# ring_indicator.net
KiCad netlist of a schematic drawn in EAGLE
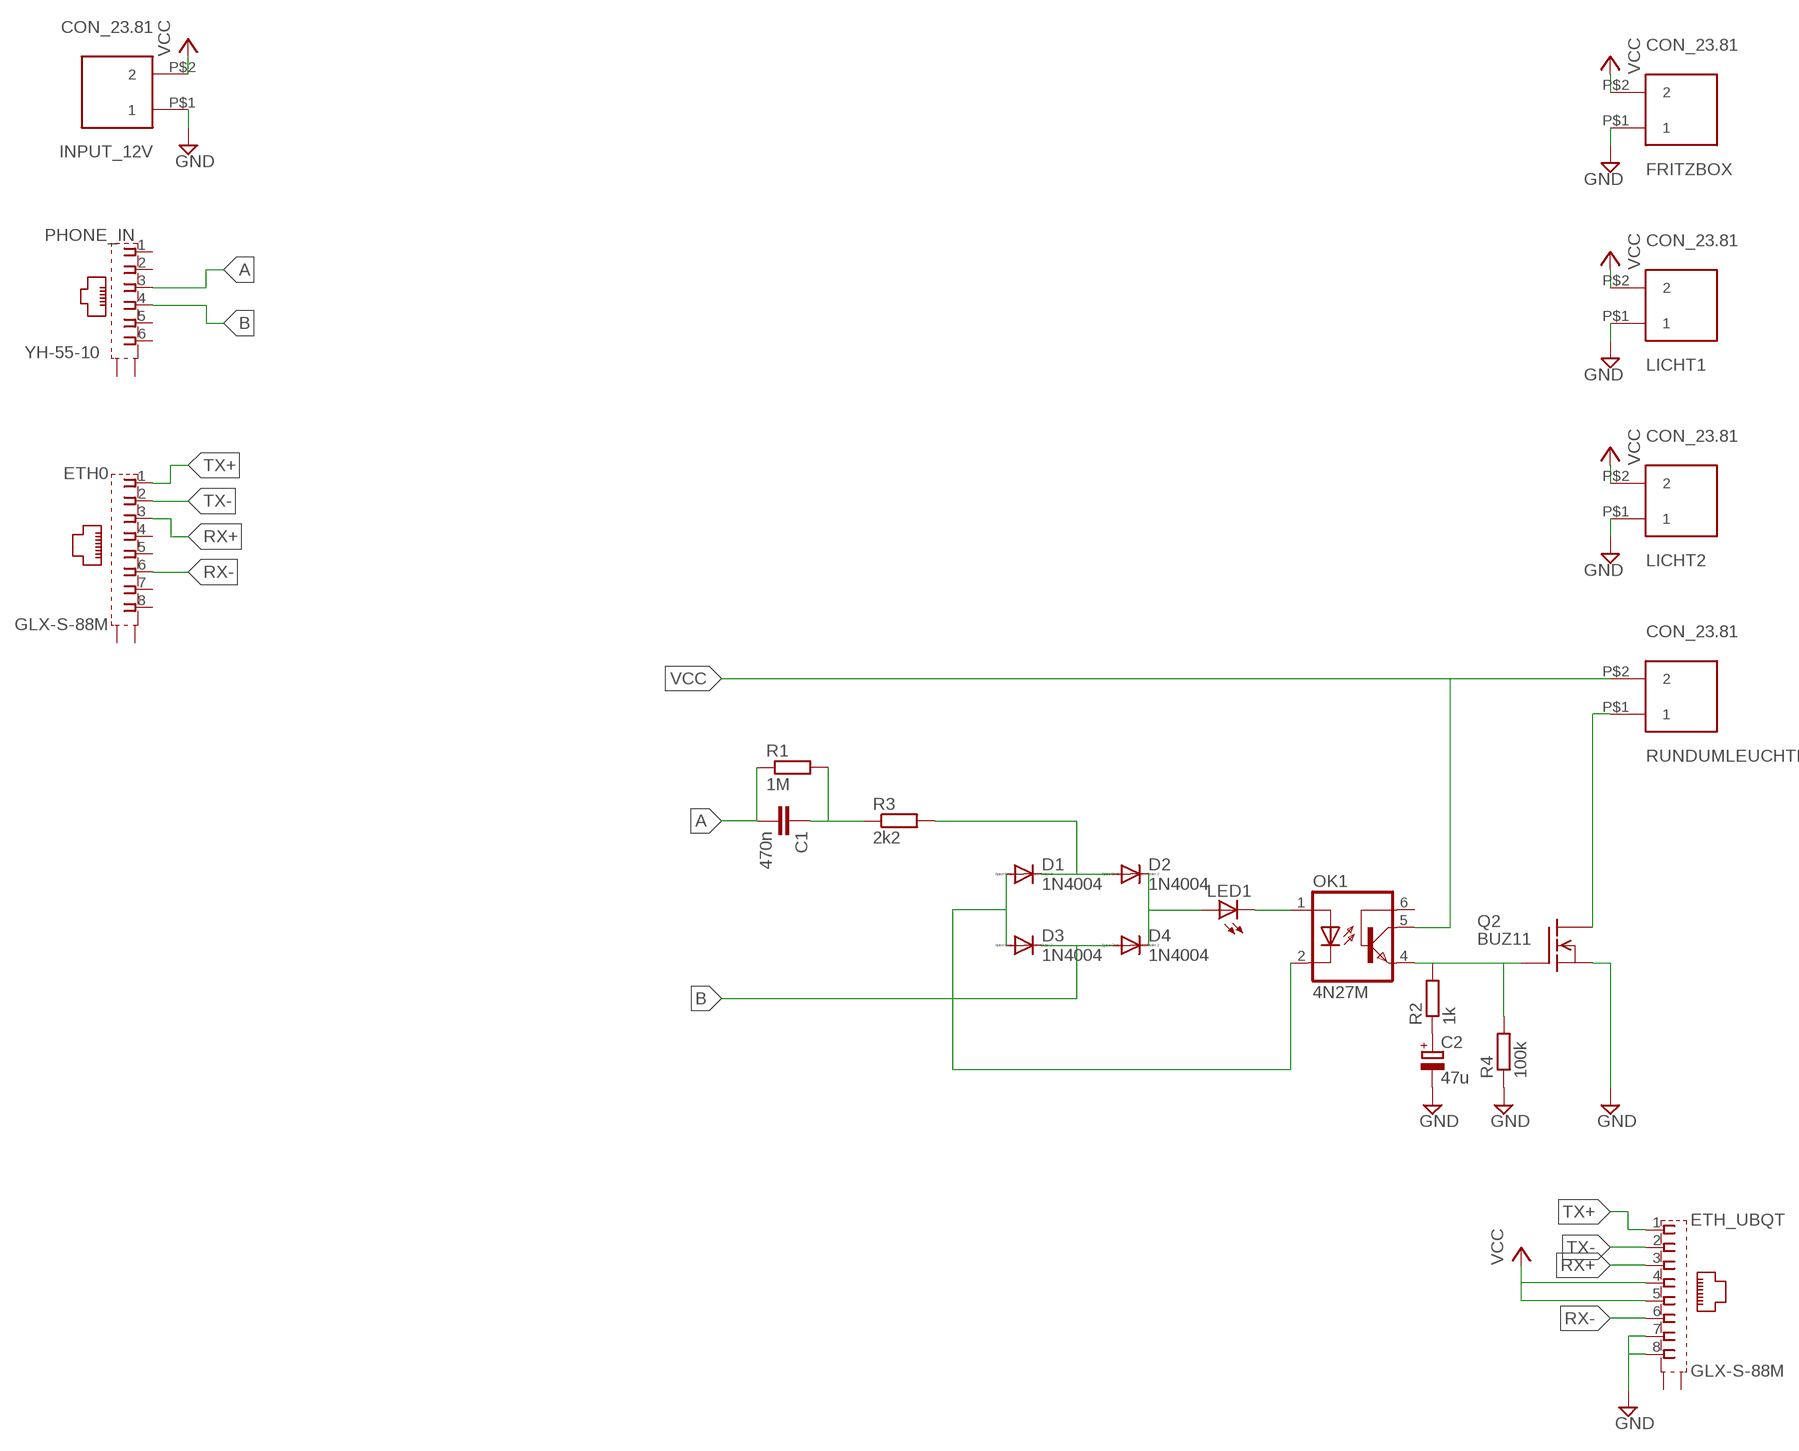
[diagram p0: schematic, sheet 1]

(export (version "E")
  (design (tool "Eeschema 10.0.6"))
  (components
    (comp (ref "C1")
      (value "470n")
      (footprint "eagle-import:C102-064X133")
      (libsource (lib "eagle-import") (part "C-EU102-064X133"))
    )
    (comp (ref "C2")
      (value "47u")
      (footprint "eagle-import:E3,5-8")
      (libsource (lib "eagle-import") (part "CPOL-EUE3.5-8"))
    )
    (comp (ref "D1")
      (value "1N4004")
      (footprint "eagle-import:DO41-10")
      (libsource (lib "eagle-import") (part "1N4004"))
    )
    (comp (ref "D2")
      (value "1N4004")
      (footprint "eagle-import:DO41-10")
      (libsource (lib "eagle-import") (part "1N4004"))
    )
    (comp (ref "D3")
      (value "1N4004")
      (footprint "eagle-import:DO41-10")
      (libsource (lib "eagle-import") (part "1N4004"))
    )
    (comp (ref "D4")
      (value "1N4004")
      (footprint "eagle-import:DO41-10")
      (libsource (lib "eagle-import") (part "1N4004"))
    )
    (comp (ref "ETH0")
      (value "GLX-S-88M")
      (footprint "eagle-import:GLX-S-88M")
      (libsource (lib "eagle-import") (part "GLX-S-88M"))
    )
    (comp (ref "ETH_UBQT")
      (value "GLX-S-88M")
      (footprint "eagle-import:GLX-S-88M")
      (libsource (lib "eagle-import") (part "GLX-S-88M"))
    )
    (comp (ref "FRITZBOX")
      (value "CON_23.81")
      (footprint "eagle-import:CON_2_3.81")
      (libsource (lib "eagle-import") (part "CON_23.81"))
    )
    (comp (ref "INPUT_12V")
      (value "CON_23.81")
      (footprint "eagle-import:CON_2_3.81")
      (libsource (lib "eagle-import") (part "CON_23.81"))
    )
    (comp (ref "LED1")
      (value "LED5MM")
      (footprint "eagle-import:LED5MM")
      (libsource (lib "eagle-import") (part "LED5MM"))
    )
    (comp (ref "LICHT1")
      (value "CON_23.81")
      (footprint "eagle-import:CON_2_3.81")
      (libsource (lib "eagle-import") (part "CON_23.81"))
    )
    (comp (ref "LICHT2")
      (value "CON_23.81")
      (footprint "eagle-import:CON_2_3.81")
      (libsource (lib "eagle-import") (part "CON_23.81"))
    )
    (comp (ref "OK1")
      (value "4N27M")
      (footprint "eagle-import:DIL06")
      (fields (field (name "MF") "FAIRCHILD SEMICONDUCTOR"))
      (libsource (lib "eagle-import") (part "4N?M27"))
    )
    (comp (ref "PHONE_IN")
      (value "YH-55-10")
      (footprint "eagle-import:YH-55-10")
      (libsource (lib "eagle-import") (part "YH-55-10"))
    )
    (comp (ref "Q2")
      (value "BUZ11")
      (footprint "eagle-import:TO220")
      (libsource (lib "eagle-import") (part "BUZ11"))
    )
    (comp (ref "R1")
      (value "1M")
      (footprint "eagle-import:0207_10")
      (libsource (lib "eagle-import") (part "R-EU_0207/10"))
    )
    (comp (ref "R2")
      (value "1k")
      (footprint "eagle-import:0207_10")
      (libsource (lib "eagle-import") (part "R-EU_0207/10"))
    )
    (comp (ref "R3")
      (value "2k2")
      (footprint "eagle-import:0207_10")
      (libsource (lib "eagle-import") (part "R-EU_0207/10"))
    )
    (comp (ref "R4")
      (value "100k")
      (footprint "eagle-import:0207_10")
      (libsource (lib "eagle-import") (part "R-EU_0207/10"))
    )
    (comp (ref "RUNDUMLEUCHTE")
      (value "CON_23.81")
      (footprint "eagle-import:CON_2_3.81")
      (libsource (lib "eagle-import") (part "CON_23.81"))
    )
  )
  (nets
    (net (code "1") (name "A") (class "Default")
      (node (ref "C1") (pin "2") (pinfunction "2_2") (pintype "passive"))
      (node (ref "PHONE_IN") (pin "3") (pinfunction "3_3") (pintype "passive"))
      (node (ref "R1") (pin "1") (pinfunction "1_1") (pintype "passive"))
    )
    (net (code "2") (name "B") (class "Default")
      (node (ref "D3") (pin "C") (pinfunction "C_C") (pintype "passive"))
      (node (ref "D4") (pin "A") (pinfunction "A_A") (pintype "passive"))
      (node (ref "PHONE_IN") (pin "4") (pinfunction "4_4") (pintype "passive"))
    )
    (net (code "3") (name "GND") (class "Default")
      (node (ref "C2") (pin "-") (pinfunction "-_-") (pintype "passive"))
      (node (ref "ETH_UBQT") (pin "7") (pinfunction "7_7") (pintype "passive"))
      (node (ref "ETH_UBQT") (pin "8") (pinfunction "8_8") (pintype "passive"))
      (node (ref "FRITZBOX") (pin "P$1") (pinfunction "1_P$1") (pintype "bidirectional"))
      (node (ref "INPUT_12V") (pin "P$1") (pinfunction "1_P$1") (pintype "bidirectional"))
      (node (ref "LICHT1") (pin "P$1") (pinfunction "1_P$1") (pintype "bidirectional"))
      (node (ref "LICHT2") (pin "P$1") (pinfunction "1_P$1") (pintype "bidirectional"))
      (node (ref "Q2") (pin "3") (pinfunction "S_3") (pintype "passive"))
      (node (ref "R4") (pin "1") (pinfunction "1_1") (pintype "passive"))
    )
    (net (code "4") (name "Net-(C1-Pad1)") (class "Default")
      (node (ref "C1") (pin "1") (pinfunction "1_1") (pintype "passive"))
      (node (ref "R1") (pin "2") (pinfunction "2_2") (pintype "passive"))
      (node (ref "R3") (pin "1") (pinfunction "1_1") (pintype "passive"))
    )
    (net (code "5") (name "Net-(C2-Pad+)") (class "Default")
      (node (ref "C2") (pin "+") (pinfunction "+_+") (pintype "passive"))
      (node (ref "R2") (pin "1") (pinfunction "1_1") (pintype "passive"))
    )
    (net (code "6") (name "Net-(D1-PadC)") (class "Default")
      (node (ref "D1") (pin "C") (pinfunction "C_C") (pintype "passive"))
      (node (ref "D2") (pin "A") (pinfunction "A_A") (pintype "passive"))
      (node (ref "R3") (pin "2") (pinfunction "2_2") (pintype "passive"))
    )
    (net (code "7") (name "Net-(D2-PadC)") (class "Default")
      (node (ref "D2") (pin "C") (pinfunction "C_C") (pintype "passive"))
      (node (ref "D4") (pin "C") (pinfunction "C_C") (pintype "passive"))
      (node (ref "LED1") (pin "A") (pinfunction "A_A") (pintype "passive"))
    )
    (net (code "8") (name "Net-(LED1-C)") (class "Default")
      (node (ref "LED1") (pin "K") (pinfunction "C_K") (pintype "passive"))
      (node (ref "OK1") (pin "1") (pinfunction "A_1") (pintype "passive"))
    )
    (net (code "9") (name "Net-(OK1-C)") (class "Default")
      (node (ref "D1") (pin "A") (pinfunction "A_A") (pintype "passive"))
      (node (ref "D3") (pin "A") (pinfunction "A_A") (pintype "passive"))
      (node (ref "OK1") (pin "2") (pinfunction "C_2") (pintype "passive"))
    )
    (net (code "10") (name "Net-(OK1-EMI)") (class "Default")
      (node (ref "OK1") (pin "4") (pinfunction "EMI_4") (pintype "passive"))
      (node (ref "Q2") (pin "1") (pinfunction "G_1") (pintype "passive"))
      (node (ref "R2") (pin "2") (pinfunction "2_2") (pintype "passive"))
      (node (ref "R4") (pin "2") (pinfunction "2_2") (pintype "passive"))
    )
    (net (code "11") (name "Net-(Q2-D)") (class "Default")
      (node (ref "Q2") (pin "2") (pinfunction "D_2") (pintype "passive"))
      (node (ref "RUNDUMLEUCHTE") (pin "P$1") (pinfunction "1_P$1") (pintype "bidirectional"))
    )
    (net (code "12") (name "RX+") (class "Default")
      (node (ref "ETH0") (pin "3") (pinfunction "3_3") (pintype "passive"))
      (node (ref "ETH_UBQT") (pin "3") (pinfunction "3_3") (pintype "passive"))
    )
    (net (code "13") (name "RX-") (class "Default")
      (node (ref "ETH0") (pin "6") (pinfunction "6_6") (pintype "passive"))
      (node (ref "ETH_UBQT") (pin "6") (pinfunction "6_6") (pintype "passive"))
    )
    (net (code "14") (name "TX+") (class "Default")
      (node (ref "ETH0") (pin "1") (pinfunction "1_1") (pintype "passive"))
      (node (ref "ETH_UBQT") (pin "1") (pinfunction "1_1") (pintype "passive"))
    )
    (net (code "15") (name "TX-") (class "Default")
      (node (ref "ETH0") (pin "2") (pinfunction "2_2") (pintype "passive"))
      (node (ref "ETH_UBQT") (pin "2") (pinfunction "2_2") (pintype "passive"))
    )
    (net (code "16") (name "VCC") (class "Default")
      (node (ref "ETH_UBQT") (pin "4") (pinfunction "4_4") (pintype "passive"))
      (node (ref "ETH_UBQT") (pin "5") (pinfunction "5_5") (pintype "passive"))
      (node (ref "FRITZBOX") (pin "P$2") (pinfunction "2_P$2") (pintype "bidirectional"))
      (node (ref "INPUT_12V") (pin "P$2") (pinfunction "2_P$2") (pintype "bidirectional"))
      (node (ref "LICHT1") (pin "P$2") (pinfunction "2_P$2") (pintype "bidirectional"))
      (node (ref "LICHT2") (pin "P$2") (pinfunction "2_P$2") (pintype "bidirectional"))
      (node (ref "OK1") (pin "5") (pinfunction "COL_5") (pintype "passive"))
      (node (ref "RUNDUMLEUCHTE") (pin "P$2") (pinfunction "2_P$2") (pintype "bidirectional"))
    )
    (net (code "17") (name "unconnected-(ETH0-Pad4)") (class "Default")
      (node (ref "ETH0") (pin "4") (pinfunction "4_4") (pintype "passive"))
    )
    (net (code "18") (name "unconnected-(ETH0-Pad5)") (class "Default")
      (node (ref "ETH0") (pin "5") (pinfunction "5_5") (pintype "passive"))
    )
    (net (code "19") (name "unconnected-(ETH0-Pad7)") (class "Default")
      (node (ref "ETH0") (pin "7") (pinfunction "7_7") (pintype "passive"))
    )
    (net (code "20") (name "unconnected-(ETH0-Pad8)") (class "Default")
      (node (ref "ETH0") (pin "8") (pinfunction "8_8") (pintype "passive"))
    )
    (net (code "21") (name "unconnected-(ETH0-PadS1)") (class "Default")
      (node (ref "ETH0") (pin "S1") (pinfunction "S1_S1") (pintype "passive"))
    )
    (net (code "22") (name "unconnected-(ETH0-PadS2)") (class "Default")
      (node (ref "ETH0") (pin "S2") (pinfunction "S2_S2") (pintype "passive"))
    )
    (net (code "23") (name "unconnected-(ETH_UBQT-PadS1)") (class "Default")
      (node (ref "ETH_UBQT") (pin "S1") (pinfunction "S1_S1") (pintype "passive"))
    )
    (net (code "24") (name "unconnected-(ETH_UBQT-PadS2)") (class "Default")
      (node (ref "ETH_UBQT") (pin "S2") (pinfunction "S2_S2") (pintype "passive"))
    )
    (net (code "25") (name "unconnected-(OK1-BAS-Pad6)") (class "Default")
      (node (ref "OK1") (pin "6") (pinfunction "BAS_6") (pintype "passive"))
    )
    (net (code "26") (name "unconnected-(PHONE_IN-Pad1)") (class "Default")
      (node (ref "PHONE_IN") (pin "1") (pinfunction "1_1") (pintype "passive"))
    )
    (net (code "27") (name "unconnected-(PHONE_IN-Pad2)") (class "Default")
      (node (ref "PHONE_IN") (pin "2") (pinfunction "2_2") (pintype "passive"))
    )
    (net (code "28") (name "unconnected-(PHONE_IN-Pad5)") (class "Default")
      (node (ref "PHONE_IN") (pin "5") (pinfunction "5_5") (pintype "passive"))
    )
    (net (code "29") (name "unconnected-(PHONE_IN-Pad6)") (class "Default")
      (node (ref "PHONE_IN") (pin "6") (pinfunction "6_6") (pintype "passive"))
    )
    (net (code "30") (name "unconnected-(PHONE_IN-S-PadS1)") (class "Default")
      (node (ref "PHONE_IN") (pin "S1") (pinfunction "S_S1") (pintype "passive"))
    )
    (net (code "31") (name "unconnected-(PHONE_IN-S-PadS2)") (class "Default")
      (node (ref "PHONE_IN") (pin "S2") (pinfunction "S_S2") (pintype "passive"))
    )
  )
)
